# TDA2003.net
KiCad netlist of a schematic drawn in Altium Designer
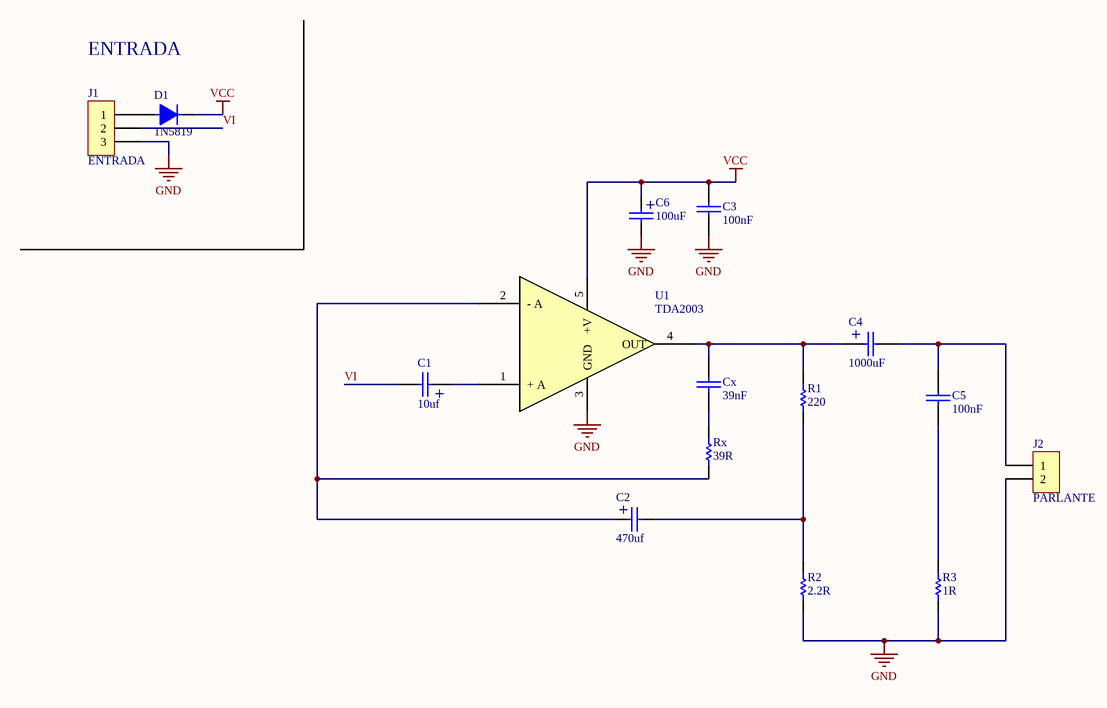
[diagram p0: TDA2003.SchDoc]

(export (version "E")
  (design (tool "Eeschema 10.0.6"))
  (components
    (comp (ref "C1") (value "10uf") (footprint "CAP100RP") (libsource (lib "Libreria4") (part "CAPPOL")))
    (comp (ref "C2")
      (value "470uf")
      (footprint "CAP300/150")
      (libsource (lib "LIBPIOIX-0314B") (part "CAPPOL"))
    )
    (comp (ref "C3") (value "100nF") (footprint "CAP100") (libsource (lib "LIBPIOIX") (part "CAP")))
    (comp (ref "C4") (value "1000uF") (footprint "CAP400RP") (libsource (lib "LIBEBAL") (part "CAPPOL")))
    (comp (ref "C5") (value "100nF") (footprint "CAP100") (libsource (lib "LIBPIOIX") (part "CAP")))
    (comp (ref "C6")
      (value "100uF")
      (footprint "CAP300/150")
      (libsource (lib "LIBPIOIX-0314B") (part "CAPPOL"))
    )
    (comp (ref "Cx") (value "39nF") (footprint "CAP100") (libsource (lib "LIBPIOIX") (part "CAP")))
    (comp (ref "D1") (value "1N5819") (footprint "DO41") (libsource (lib "Libreria4") (part "DIODO")))
    (comp (ref "J1")
      (value "ENTRADA")
      (footprint "BORNERA3")
      (libsource (lib "Libreria4") (part "BORNERA 3"))
    )
    (comp (ref "J2") (value "PARLANTE") (footprint "SIP2") (libsource (lib "Libreria4") (part "CON2")))
    (comp (ref "R1") (value "220") (footprint "RES400") (libsource (lib "Libreria4") (part "RES")))
    (comp (ref "R2") (value "2.2R") (footprint "RES400") (libsource (lib "Libreria4") (part "RES")))
    (comp (ref "R3") (value "1R") (footprint "RES400") (libsource (lib "Libreria4") (part "RES")))
    (comp (ref "Rx") (value "39R") (footprint "RES400") (libsource (lib "Libreria4") (part "RES")))
    (comp (ref "U1")
      (value "TDA2003")
      (footprint "TO220B")
      (description "TDA2003 + DISIPADOR, MICA Y TORNILLO")
      (libsource (lib "Libreria Buena Onda V5") (part "TDA2003"))
    )
  )
  (nets
    (net (code "1") (name "/VI") (class "Default")
      (node (ref "C1") (pin "2") (pinfunction "2_2") (pintype "passive"))
      (node (ref "J1") (pin "2") (pinfunction "2_2") (pintype "passive"))
    )
    (net (code "2") (name "GND") (class "Default")
      (node (ref "C3") (pin "2") (pinfunction "2_2") (pintype "passive"))
      (node (ref "C6") (pin "2") (pinfunction "2_2") (pintype "passive"))
      (node (ref "J1") (pin "3") (pinfunction "3_3") (pintype "passive"))
      (node (ref "J2") (pin "2") (pinfunction "2_2") (pintype "passive"))
      (node (ref "R2") (pin "1") (pinfunction "1_1") (pintype "passive"))
      (node (ref "R3") (pin "1") (pinfunction "1_1") (pintype "passive"))
      (node (ref "U1") (pin "3") (pinfunction "GND_3") (pintype "passive"))
    )
    (net (code "3") (name "Net-(C2-Pad2)") (class "Default")
      (node (ref "C2") (pin "2") (pinfunction "2_2") (pintype "passive"))
      (node (ref "R1") (pin "1") (pinfunction "1_1") (pintype "passive"))
      (node (ref "R2") (pin "2") (pinfunction "2_2") (pintype "passive"))
    )
    (net (code "4") (name "Net-(C4-Pad2)") (class "Default")
      (node (ref "C4") (pin "2") (pinfunction "2_2") (pintype "passive"))
      (node (ref "C5") (pin "1") (pinfunction "1_1") (pintype "passive"))
      (node (ref "J2") (pin "1") (pinfunction "1_1") (pintype "passive"))
    )
    (net (code "5") (name "Net-(C5-Pad2)") (class "Default")
      (node (ref "C5") (pin "2") (pinfunction "2_2") (pintype "passive"))
      (node (ref "R3") (pin "2") (pinfunction "2_2") (pintype "passive"))
    )
    (net (code "6") (name "Net-(Cx-Pad2)") (class "Default")
      (node (ref "Cx") (pin "2") (pinfunction "2_2") (pintype "passive"))
      (node (ref "Rx") (pin "2") (pinfunction "2_2") (pintype "passive"))
    )
    (net (code "7") (name "Net-(D1-Pad1)") (class "Default")
      (node (ref "D1") (pin "1") (pinfunction "1_1") (pintype "passive"))
      (node (ref "J1") (pin "1") (pinfunction "1_1") (pintype "passive"))
    )
    (net (code "8") (name "Net-(U1-+_A)") (class "Default")
      (node (ref "C1") (pin "1") (pinfunction "1_1") (pintype "passive"))
      (node (ref "U1") (pin "1") (pinfunction "+_A_1") (pintype "passive"))
    )
    (net (code "9") (name "Net-(U1--_A)") (class "Default")
      (node (ref "C2") (pin "1") (pinfunction "1_1") (pintype "passive"))
      (node (ref "Rx") (pin "1") (pinfunction "1_1") (pintype "passive"))
      (node (ref "U1") (pin "2") (pinfunction "-_A_2") (pintype "passive"))
    )
    (net (code "10") (name "Net-(U1-OUT)") (class "Default")
      (node (ref "C4") (pin "1") (pinfunction "1_1") (pintype "passive"))
      (node (ref "Cx") (pin "1") (pinfunction "1_1") (pintype "passive"))
      (node (ref "R1") (pin "2") (pinfunction "2_2") (pintype "passive"))
      (node (ref "U1") (pin "4") (pinfunction "OUT_4") (pintype "passive"))
    )
    (net (code "11") (name "VCC") (class "Default")
      (node (ref "C3") (pin "1") (pinfunction "1_1") (pintype "passive"))
      (node (ref "C6") (pin "1") (pinfunction "1_1") (pintype "passive"))
      (node (ref "D1") (pin "2") (pinfunction "2_2") (pintype "passive"))
      (node (ref "U1") (pin "5") (pinfunction "+V_5") (pintype "passive"))
    )
  )
)
